# Electrode.net
KiCad netlist of a schematic drawn in Altium Designer
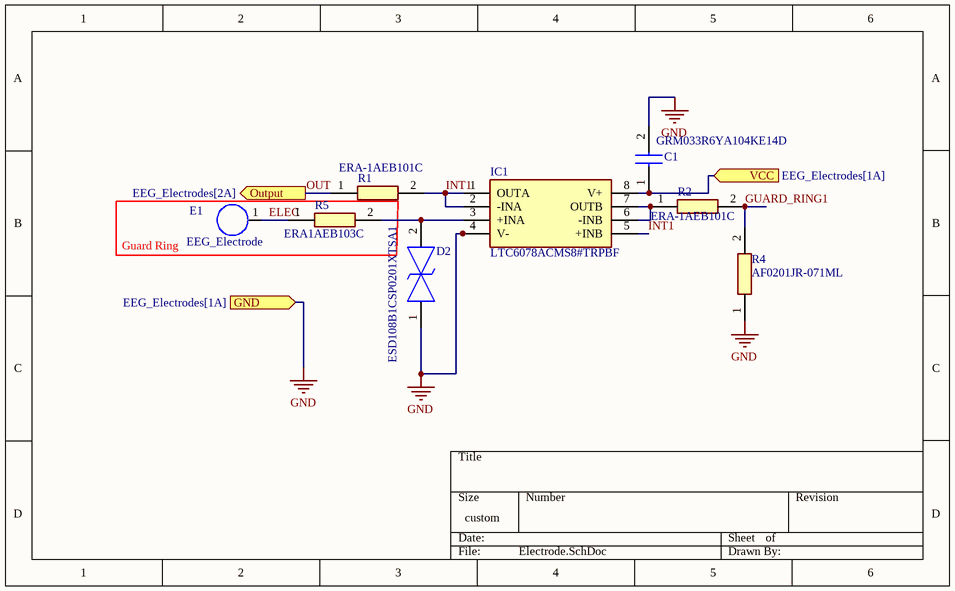
[diagram p0: Electrode.SchDoc]

(export (version "E")
  (design (tool "Eeschema 10.0.6"))
  (components
    (comp (ref "C1")
      (value "GRM033R6YA104KE14D")
      (footprint "SamacSys:CAPC0603X33N")
      (description "Capacitor 0.1uF 0201")
      (fields (field (name "MOUSER PART NUMBER") "81-GRM33R6YA104KE14D"))
      (libsource (lib "*") (part "GRM033R6YA104KE14D"))
    )
    (comp (ref "D2")
      (value "ESD108B1CSP0201XTSA1")
      (footprint "SamacSys:ESD108B1CSP0201XTSA1")
      (description "TVS Diode (Bi-directional)")
      (fields (field (name "MOUSER PART NUMBER") "726-ESD108B1CSP0201X"))
      (libsource (lib "SamacSys") (part "ESD108B1CSP0201XTSA1"))
    )
    (comp (ref "E1")
      (value "EEG_Electrode")
      (footprint "EEG_Electrode")
      (libsource (lib "Rishabh_Schematic_Library") (part "EEG_Electrode"))
    )
    (comp (ref "IC1")
      (value "LTC6078ACMS8#TRPBF")
      (footprint "SamacSys:SOP65P490X110-8N")
      (description "Integrated Circuit")
      (fields (field (name "MOUSER PART NUMBER") "584-C6078ACMS8TRPBF"))
      (libsource (lib "*") (part "LTC6078ACMS8#TRPBF"))
    )
    (comp (ref "R1")
      (value "ERA-1AEB101C")
      (footprint "SamacSys:ERA1A_(0201)")
      (description "Resistor 100 ohms")
      (fields (field (name "MOUSER PART NUMBER") "667-ERA-1AEB101C"))
      (libsource (lib "*") (part "ERA-1AEB101C"))
    )
    (comp (ref "R2")
      (value "ERA-1AEB101C")
      (footprint "SamacSys:ERA1A_(0201)")
      (description "Resistor 100 ohms")
      (fields (field (name "MOUSER PART NUMBER") "667-ERA-1AEB101C"))
      (libsource (lib "*") (part "ERA-1AEB101C"))
    )
    (comp (ref "R4")
      (value "AF0201JR-071ML")
      (footprint "SamacSys:ERA1A_(0201)")
      (description "Resistor 1M")
      (fields
        (field (name "MANUFACTURER_PART_NUMBER") "ERA-1AEB101C")
        (field (name "MOUSER PART NUMBER") "667-ERA-1AEB101C")
      )
      (libsource (lib "") (part "ERA-1AEB101C_1"))
    )
    (comp (ref "R5")
      (value "ERA1AEB103C")
      (footprint "SamacSys:ERA1A_(0201)")
      (description "Resistor 10k")
      (libsource (lib "SamacSys") (part "ERA1AEB103C"))
    )
  )
  (nets
    (net (code "1") (name "/ELEC") (class "Default")
      (node (ref "E1") (pin "1") (pintype "passive"))
      (node (ref "R5") (pin "1") (pinfunction "1_1") (pintype "passive"))
    )
    (net (code "2") (name "/GUARD_RING1") (class "Default")
      (node (ref "R2") (pin "2") (pinfunction "2_2") (pintype "passive"))
      (node (ref "R4") (pin "2") (pinfunction "2_2") (pintype "passive"))
    )
    (net (code "3") (name "/INT1") (class "Default")
      (node (ref "IC1") (pin "1") (pinfunction "OUTA_1") (pintype "passive"))
      (node (ref "IC1") (pin "2") (pinfunction "-INA_2") (pintype "passive"))
      (node (ref "IC1") (pin "5") (pinfunction "+INB_5") (pintype "passive"))
      (node (ref "R1") (pin "2") (pinfunction "2_2") (pintype "passive"))
    )
    (net (code "4") (name "/OUT") (class "Default")
      (node (ref "R1") (pin "1") (pinfunction "1_1") (pintype "passive"))
    )
    (net (code "5") (name "/VCC") (class "Default")
      (node (ref "C1") (pin "1") (pinfunction "1_1") (pintype "passive"))
      (node (ref "IC1") (pin "8") (pinfunction "V+_8") (pintype "passive"))
    )
    (net (code "6") (name "GND") (class "Default")
      (node (ref "C1") (pin "2") (pinfunction "2_2") (pintype "passive"))
      (node (ref "D2") (pin "1") (pinfunction "1_1") (pintype "passive"))
      (node (ref "IC1") (pin "4") (pinfunction "V-_4") (pintype "passive"))
      (node (ref "R4") (pin "1") (pinfunction "1_1") (pintype "passive"))
    )
    (net (code "7") (name "Net-(IC1-+INA)") (class "Default")
      (node (ref "D2") (pin "2") (pinfunction "2_2") (pintype "passive"))
      (node (ref "IC1") (pin "3") (pinfunction "+INA_3") (pintype "passive"))
      (node (ref "R5") (pin "2") (pinfunction "2_2") (pintype "passive"))
    )
    (net (code "8") (name "Net-(IC1--INB)") (class "Default")
      (node (ref "IC1") (pin "6") (pinfunction "-INB_6") (pintype "passive"))
      (node (ref "IC1") (pin "7") (pinfunction "OUTB_7") (pintype "passive"))
      (node (ref "R2") (pin "1") (pinfunction "1_1") (pintype "passive"))
    )
  )
)
